# PCB_uC_Slave_Switch.net
KiCad netlist of a schematic drawn in Altium Designer
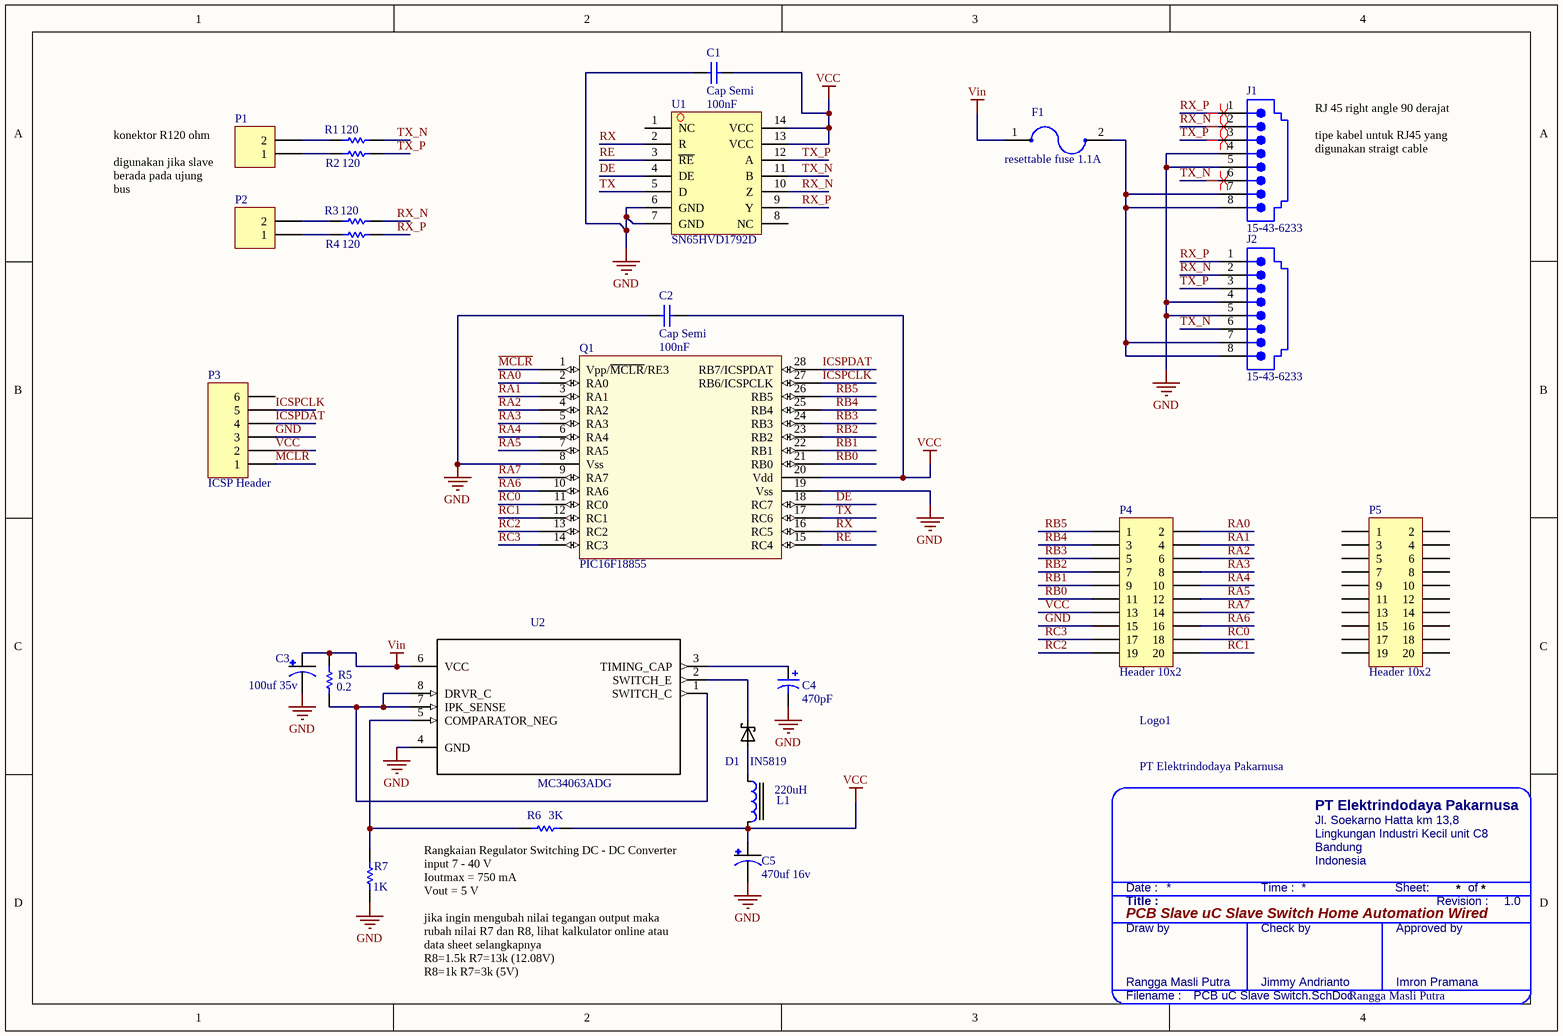
[diagram p0: PCB uC Slave Switch.SchDoc]

(export (version "E")
  (design (tool "Eeschema 10.0.6"))
  (components
    (comp (ref "C1")
      (value "Cap Semi")
      (footprint "CAPC2012M")
      (description "Capacitor (Semiconductor SIM Model)")
      (fields (field (name "ALTIUM_VALUE") "100nF") (field (name "PUBLISHER") "Altium Limited"))
      (libsource (lib "Miscellaneous Devices") (part "Cap Semi"))
    )
    (comp (ref "C2")
      (value "Cap Semi")
      (footprint "CAPC2012M")
      (description "Capacitor (Semiconductor SIM Model)")
      (fields (field (name "ALTIUM_VALUE") "100nF") (field (name "PUBLISHER") "Altium Limited"))
      (libsource (lib "Miscellaneous Devices") (part "Cap Semi"))
    )
    (comp (ref "C3")
      (value "100uf 35v")
      (footprint "OSCON_SVPF_6.3MM")
      (description "Cap, Alu Elec, 100uf, 50v, Smd")
      (fields (field (name "MP") "EDK107M050A9MAA") (field (name "MF") "Kemet"))
      (libsource (lib "RMPLib") (part "EDK107M050A9MAA"))
    )
    (comp (ref "C4")
      (value "470pF")
      (footprint "CAPC2012M")
      (description "Polarized Capacitor (Surface Mount)")
      (fields (field (name "Comment") "Cap Pol3") (field (name "PUBLISHER") "Altium Limited"))
      (libsource (lib "Miscellaneous Devices") (part "Cap Pol3"))
    )
    (comp (ref "C5")
      (value "470uf 16v")
      (footprint "CAPAE1030X1200_EEE-FC1C471AP(Primary)")
      (description "Cap, Alu Elec, 100uf, 50v, Smd")
      (fields (field (name "MP") "EDK107M050A9MAA") (field (name "MF") "Kemet"))
      (libsource (lib "RMPLib") (part "EDK107M050A9MAA"))
    )
    (comp (ref "D1")
      (value "IN5819")
      (footprint "DO-214AC_SS14(Primary)")
      (description "1a 40v Smd Schottky Rectifier")
      (fields (field (name "MF") "Taiwan Semiconductor") (field (name "MP") "SS14"))
      (libsource (lib "SS14") (part "SS14"))
    )
    (comp (ref "F1")
      (value "resettable fuse 1.1A")
      (footprint "0805")
      (description "resettable fuse 1.1A 0805")
      (fields (field (name "MF") "Littelfuse"))
      (libsource (lib "resettable fuse 1.1a 0805 ") (part "resettable fuse 1.1A 0805"))
    )
    (comp (ref "J1")
      (value "15-43-6233")
      (footprint "15-43-6233")
      (description "Right Angle, Standard Profile, RJ45-Keyed, Flange Mount PCB Jack")
      (fields (field (name "PUBLISHER") "Altium Limited"))
      (libsource (lib "newmolex modular") (part "15-43-6233"))
    )
    (comp (ref "J2")
      (value "15-43-6233")
      (footprint "15-43-6233")
      (description "Right Angle, Standard Profile, RJ45-Keyed, Flange Mount PCB Jack")
      (fields (field (name "PUBLISHER") "Altium Limited"))
      (libsource (lib "newmolex modular") (part "15-43-6233"))
    )
    (comp (ref "L1")
      (value "220uH")
      (footprint "CDRH104R")
      (description "Inductor Power Shielded Drum Core 220uH")
      (fields (field (name "MF") "Sumida") (field (name "MP") "CDRH104RNP-101NC"))
      (libsource (lib "CDRH104R") (part "CDRH104R"))
    )
    (comp (ref "Logo1")
      (value "PT Elektrindodaya Pakarnusa")
      (footprint "ElsaLogoTop")
      (description "Elsa Company Logo")
      (fields (field (name "CREATE BY") "Jimmy Andrianto"))
      (libsource (lib "JimmyLib14E") (part "ElsaLogoTopOverlay"))
    )
    (comp (ref "P1")
      (value "Header 2")
      (footprint "HDR1X2")
      (description "Header, 2-Pin")
      (fields (field (name "PUBLISHER") "Altium Limited"))
      (libsource (lib "custom connectors") (part "Header 2"))
    )
    (comp (ref "P2")
      (value "Header 2")
      (footprint "HDR1X2")
      (description "Header, 2-Pin")
      (fields (field (name "PUBLISHER") "Altium Limited"))
      (libsource (lib "custom connectors") (part "Header 2"))
    )
    (comp (ref "P3")
      (value "ICSP Header")
      (footprint "HDR1X6")
      (description "Header, 6-Pin")
      (fields (field (name "PUBLISHER") "Altium Limited"))
      (libsource (lib "custom connectors") (part "Header 6"))
    )
    (comp (ref "P4")
      (value "Header 10x2")
      (footprint "HDR2X10 pitch 2mm hole")
      (description "Header, 14-Pin, Dual row")
      (fields (field (name "PUBLISHER") "Altium Limited"))
      (libsource (lib "RMPLib") (part "Header 10x2"))
    )
    (comp (ref "P5")
      (value "Header 10x2")
      (footprint "HDR2X10 pitch 2mm hole")
      (description "Header, 14-Pin, Dual row")
      (fields (field (name "PUBLISHER") "Altium Limited"))
      (libsource (lib "RMPLib") (part "Header 10x2"))
    )
    (comp (ref "Q1")
      (value "PIC16F18855")
      (footprint "SOP65P780X200-28N")
      (description "PIC16F18855-SSOP 28 pin")
      (libsource (lib "PIC16F18855") (part "PIC16F18855"))
    )
    (comp (ref "R1")
      (value "120")
      (footprint "RESC1608M")
      (description "Resistor")
      (fields (field (name "Comment") "Res1") (field (name "PUBLISHER") "Altium Limited"))
      (libsource (lib "Miscellaneous Devices") (part "Res1"))
    )
    (comp (ref "R2")
      (value "120")
      (footprint "RESC1608M")
      (description "Resistor")
      (fields (field (name "Comment") "Res1") (field (name "PUBLISHER") "Altium Limited"))
      (libsource (lib "Miscellaneous Devices") (part "Res1"))
    )
    (comp (ref "R3")
      (value "120")
      (footprint "RESC1608M")
      (description "Resistor")
      (fields (field (name "Comment") "Res1") (field (name "PUBLISHER") "Altium Limited"))
      (libsource (lib "Miscellaneous Devices") (part "Res1"))
    )
    (comp (ref "R4")
      (value "120")
      (footprint "RESC1608M")
      (description "Resistor")
      (fields (field (name "Comment") "Res1") (field (name "PUBLISHER") "Altium Limited"))
      (libsource (lib "Miscellaneous Devices") (part "Res1"))
    )
    (comp (ref "R5")
      (value "0.2")
      (footprint "6-0805_N")
      (description "Resistor")
      (fields (field (name "Comment") "Res1") (field (name "PUBLISHER") "Altium Limited"))
      (libsource (lib "Miscellaneous Devices") (part "Res1"))
    )
    (comp (ref "R6")
      (value "3K")
      (footprint "RESC1608M")
      (description "Resistor")
      (fields (field (name "Comment") "Res1") (field (name "PUBLISHER") "Altium Limited"))
      (libsource (lib "Miscellaneous Devices") (part "Res1"))
    )
    (comp (ref "R7")
      (value "1K")
      (footprint "RESC1608M")
      (description "Resistor")
      (fields (field (name "Comment") "Res1") (field (name "PUBLISHER") "Altium Limited"))
      (libsource (lib "Miscellaneous Devices") (part "Res1"))
    )
    (comp (ref "U1")
      (value "SN65HVD1792D")
      (footprint "R-PDSO-G14")
      (libsource (lib "ranggalib") (part "SN65HVD1792D"))
    )
    (comp (ref "U2")
      (value "MC34063ADG")
      (footprint "SOIC127P600X175-8N")
      (description "MC34063A Series 40V 1.5A 100kHz Step-Up/Down/Inverting Switching Regulator-SOIC8")
      (fields (field (name "MF") "ON Semiconductor"))
      (libsource (lib "MC34063ADG") (part "MC34063ADG"))
    )
  )
  (nets
    (net (code "1") (name "/DE") (class "Default")
      (node (ref "Q1") (pin "18") (pinfunction "RC7_18") (pintype "bidirectional"))
      (node (ref "U1") (pin "4") (pinfunction "DE_4") (pintype "passive"))
    )
    (net (code "2") (name "/ICSPCLK") (class "Default")
      (node (ref "P3") (pin "5") (pinfunction "5_5") (pintype "passive"))
      (node (ref "Q1") (pin "27") (pinfunction "RB6/ICSPCLK_27") (pintype "bidirectional"))
    )
    (net (code "3") (name "/ICSPDAT") (class "Default")
      (node (ref "P3") (pin "4") (pinfunction "4_4") (pintype "passive"))
      (node (ref "Q1") (pin "28") (pinfunction "RB7/ICSPDAT_28") (pintype "bidirectional"))
    )
    (net (code "4") (name "/RA0") (class "Default")
      (node (ref "P4") (pin "2") (pinfunction "2_2") (pintype "passive"))
      (node (ref "Q1") (pin "2") (pinfunction "RA0_2") (pintype "bidirectional"))
    )
    (net (code "5") (name "/RA1") (class "Default")
      (node (ref "P4") (pin "4") (pinfunction "4_4") (pintype "passive"))
      (node (ref "Q1") (pin "3") (pinfunction "RA1_3") (pintype "bidirectional"))
    )
    (net (code "6") (name "/RA2") (class "Default")
      (node (ref "P4") (pin "6") (pinfunction "6_6") (pintype "passive"))
      (node (ref "Q1") (pin "4") (pinfunction "RA2_4") (pintype "bidirectional"))
    )
    (net (code "7") (name "/RA3") (class "Default")
      (node (ref "P4") (pin "8") (pinfunction "8_8") (pintype "passive"))
      (node (ref "Q1") (pin "5") (pinfunction "RA3_5") (pintype "bidirectional"))
    )
    (net (code "8") (name "/RA4") (class "Default")
      (node (ref "P4") (pin "10") (pinfunction "10_10") (pintype "passive"))
      (node (ref "Q1") (pin "6") (pinfunction "RA4_6") (pintype "bidirectional"))
    )
    (net (code "9") (name "/RA5") (class "Default")
      (node (ref "P4") (pin "12") (pinfunction "12_12") (pintype "passive"))
      (node (ref "Q1") (pin "7") (pinfunction "RA5_7") (pintype "bidirectional"))
    )
    (net (code "10") (name "/RA6") (class "Default")
      (node (ref "P4") (pin "16") (pinfunction "16_16") (pintype "passive"))
      (node (ref "Q1") (pin "10") (pinfunction "RA6_10") (pintype "bidirectional"))
    )
    (net (code "11") (name "/RA7") (class "Default")
      (node (ref "P4") (pin "14") (pinfunction "14_14") (pintype "passive"))
      (node (ref "Q1") (pin "9") (pinfunction "RA7_9") (pintype "bidirectional"))
    )
    (net (code "12") (name "/RB0") (class "Default")
      (node (ref "P4") (pin "11") (pinfunction "11_11") (pintype "passive"))
      (node (ref "Q1") (pin "21") (pinfunction "RB0_21") (pintype "bidirectional"))
    )
    (net (code "13") (name "/RB1") (class "Default")
      (node (ref "P4") (pin "9") (pinfunction "9_9") (pintype "passive"))
      (node (ref "Q1") (pin "22") (pinfunction "RB1_22") (pintype "bidirectional"))
    )
    (net (code "14") (name "/RB2") (class "Default")
      (node (ref "P4") (pin "7") (pinfunction "7_7") (pintype "passive"))
      (node (ref "Q1") (pin "23") (pinfunction "RB2_23") (pintype "bidirectional"))
    )
    (net (code "15") (name "/RB3") (class "Default")
      (node (ref "P4") (pin "5") (pinfunction "5_5") (pintype "passive"))
      (node (ref "Q1") (pin "24") (pinfunction "RB3_24") (pintype "bidirectional"))
    )
    (net (code "16") (name "/RB4") (class "Default")
      (node (ref "P4") (pin "3") (pinfunction "3_3") (pintype "passive"))
      (node (ref "Q1") (pin "25") (pinfunction "RB4_25") (pintype "bidirectional"))
    )
    (net (code "17") (name "/RB5") (class "Default")
      (node (ref "P4") (pin "1") (pinfunction "1_1") (pintype "passive"))
      (node (ref "Q1") (pin "26") (pinfunction "RB5_26") (pintype "bidirectional"))
    )
    (net (code "18") (name "/RC0") (class "Default")
      (node (ref "P4") (pin "18") (pinfunction "18_18") (pintype "passive"))
      (node (ref "Q1") (pin "11") (pinfunction "RC0_11") (pintype "bidirectional"))
    )
    (net (code "19") (name "/RC1") (class "Default")
      (node (ref "P4") (pin "20") (pinfunction "20_20") (pintype "passive"))
      (node (ref "Q1") (pin "12") (pinfunction "RC1_12") (pintype "bidirectional"))
    )
    (net (code "20") (name "/RC2") (class "Default")
      (node (ref "P4") (pin "19") (pinfunction "19_19") (pintype "passive"))
      (node (ref "Q1") (pin "13") (pinfunction "RC2_13") (pintype "bidirectional"))
    )
    (net (code "21") (name "/RC3") (class "Default")
      (node (ref "P4") (pin "17") (pinfunction "17_17") (pintype "passive"))
      (node (ref "Q1") (pin "14") (pinfunction "RC3_14") (pintype "bidirectional"))
    )
    (net (code "22") (name "/RE") (class "Default")
      (node (ref "Q1") (pin "15") (pinfunction "RC4_15") (pintype "bidirectional"))
      (node (ref "U1") (pin "3") (pinfunction "~{RE}_3") (pintype "passive"))
    )
    (net (code "23") (name "/RX") (class "Default")
      (node (ref "Q1") (pin "16") (pinfunction "RC5_16") (pintype "bidirectional"))
      (node (ref "U1") (pin "2") (pinfunction "R_2") (pintype "passive"))
    )
    (net (code "24") (name "/RX_N") (class "Default")
      (node (ref "J1") (pin "2") (pinfunction "2_2") (pintype "passive"))
      (node (ref "J2") (pin "2") (pinfunction "2_2") (pintype "passive"))
      (node (ref "R3") (pin "2") (pinfunction "2_2") (pintype "passive"))
      (node (ref "U1") (pin "10") (pinfunction "Z_10") (pintype "passive"))
    )
    (net (code "25") (name "/RX_P") (class "Default")
      (node (ref "J1") (pin "1") (pinfunction "1_1") (pintype "passive"))
      (node (ref "J2") (pin "1") (pinfunction "1_1") (pintype "passive"))
      (node (ref "R4") (pin "2") (pinfunction "2_2") (pintype "passive"))
      (node (ref "U1") (pin "9") (pinfunction "Y_9") (pintype "passive"))
    )
    (net (code "26") (name "/TX") (class "Default")
      (node (ref "Q1") (pin "17") (pinfunction "RC6_17") (pintype "bidirectional"))
      (node (ref "U1") (pin "5") (pinfunction "D_5") (pintype "passive"))
    )
    (net (code "27") (name "/TX_N") (class "Default")
      (node (ref "J1") (pin "6") (pinfunction "6_6") (pintype "passive"))
      (node (ref "J2") (pin "6") (pinfunction "6_6") (pintype "passive"))
      (node (ref "R1") (pin "2") (pinfunction "2_2") (pintype "passive"))
      (node (ref "U1") (pin "11") (pinfunction "B_11") (pintype "passive"))
    )
    (net (code "28") (name "/TX_P") (class "Default")
      (node (ref "J1") (pin "3") (pinfunction "3_3") (pintype "passive"))
      (node (ref "J2") (pin "3") (pinfunction "3_3") (pintype "passive"))
      (node (ref "R2") (pin "2") (pinfunction "2_2") (pintype "passive"))
      (node (ref "U1") (pin "12") (pinfunction "A_12") (pintype "passive"))
    )
    (net (code "29") (name "/~{MCLR}") (class "Default")
      (node (ref "P3") (pin "1") (pinfunction "1_1") (pintype "passive"))
      (node (ref "Q1") (pin "1") (pinfunction "Vpp/~{MCLR}/RE3_1") (pintype "bidirectional"))
    )
    (net (code "30") (name "GND") (class "Default")
      (node (ref "C1") (pin "1") (pinfunction "1_1") (pintype "passive"))
      (node (ref "C2") (pin "1") (pinfunction "1_1") (pintype "passive"))
      (node (ref "C3") (pin "NEG") (pinfunction "NEG_NEG") (pintype "passive"))
      (node (ref "C4") (pin "2") (pinfunction "2_2") (pintype "passive"))
      (node (ref "C5") (pin "NEG") (pinfunction "NEG_NEG") (pintype "passive"))
      (node (ref "J1") (pin "4") (pinfunction "4_4") (pintype "passive"))
      (node (ref "J1") (pin "5") (pinfunction "5_5") (pintype "passive"))
      (node (ref "J2") (pin "4") (pinfunction "4_4") (pintype "passive"))
      (node (ref "J2") (pin "5") (pinfunction "5_5") (pintype "passive"))
      (node (ref "P3") (pin "3") (pinfunction "3_3") (pintype "passive"))
      (node (ref "P4") (pin "15") (pinfunction "15_15") (pintype "passive"))
      (node (ref "Q1") (pin "19") (pinfunction "Vss_19") (pintype "power_in"))
      (node (ref "Q1") (pin "8") (pinfunction "Vss_8") (pintype "power_in"))
      (node (ref "R7") (pin "1") (pinfunction "1_1") (pintype "passive"))
      (node (ref "U1") (pin "6") (pinfunction "GND_6") (pintype "passive"))
      (node (ref "U1") (pin "7") (pinfunction "GND_7") (pintype "passive"))
      (node (ref "U2") (pin "4") (pinfunction "GND_4") (pintype "passive"))
    )
    (net (code "31") (name "Net-(D1-PadA)") (class "Default")
      (node (ref "D1") (pin "A") (pinfunction "A_A") (pintype "passive"))
      (node (ref "L1") (pin "1") (pinfunction "1_1") (pintype "passive"))
    )
    (net (code "32") (name "Net-(F1-Pad2)") (class "Default")
      (node (ref "F1") (pin "2") (pinfunction "2_2") (pintype "passive"))
      (node (ref "J1") (pin "7") (pinfunction "7_7") (pintype "passive"))
      (node (ref "J1") (pin "8") (pinfunction "8_8") (pintype "passive"))
      (node (ref "J2") (pin "7") (pinfunction "7_7") (pintype "passive"))
      (node (ref "J2") (pin "8") (pinfunction "8_8") (pintype "passive"))
    )
    (net (code "33") (name "Net-(P1-Pad1)") (class "Default")
      (node (ref "P1") (pin "1") (pinfunction "1_1") (pintype "passive"))
      (node (ref "R2") (pin "1") (pinfunction "1_1") (pintype "passive"))
    )
    (net (code "34") (name "Net-(P1-Pad2)") (class "Default")
      (node (ref "P1") (pin "2") (pinfunction "2_2") (pintype "passive"))
      (node (ref "R1") (pin "1") (pinfunction "1_1") (pintype "passive"))
    )
    (net (code "35") (name "Net-(P2-Pad1)") (class "Default")
      (node (ref "P2") (pin "1") (pinfunction "1_1") (pintype "passive"))
      (node (ref "R4") (pin "1") (pinfunction "1_1") (pintype "passive"))
    )
    (net (code "36") (name "Net-(P2-Pad2)") (class "Default")
      (node (ref "P2") (pin "2") (pinfunction "2_2") (pintype "passive"))
      (node (ref "R3") (pin "1") (pinfunction "1_1") (pintype "passive"))
    )
    (net (code "37") (name "Net-(U2-COMPARATOR_NEG)") (class "Default")
      (node (ref "R6") (pin "1") (pinfunction "1_1") (pintype "passive"))
      (node (ref "R7") (pin "2") (pinfunction "2_2") (pintype "passive"))
      (node (ref "U2") (pin "5") (pinfunction "COMPARATOR_NEG_5") (pintype "input"))
    )
    (net (code "38") (name "Net-(U2-DRVR_C)") (class "Default")
      (node (ref "R5") (pin "1") (pinfunction "1_1") (pintype "passive"))
      (node (ref "U2") (pin "1") (pinfunction "SWITCH_C_1") (pintype "output"))
      (node (ref "U2") (pin "7") (pinfunction "IPK_SENSE_7") (pintype "input"))
      (node (ref "U2") (pin "8") (pinfunction "DRVR_C_8") (pintype "input"))
    )
    (net (code "39") (name "Net-(U2-SWITCH_E)") (class "Default")
      (node (ref "D1") (pin "C") (pinfunction "C_C") (pintype "passive"))
      (node (ref "U2") (pin "2") (pinfunction "SWITCH_E_2") (pintype "output"))
    )
    (net (code "40") (name "Net-(U2-TIMING_CAP)") (class "Default")
      (node (ref "C4") (pin "1") (pinfunction "1_1") (pintype "passive"))
      (node (ref "U2") (pin "3") (pinfunction "TIMING_CAP_3") (pintype "output"))
    )
    (net (code "41") (name "VCC") (class "Default")
      (node (ref "C1") (pin "2") (pinfunction "2_2") (pintype "passive"))
      (node (ref "C2") (pin "2") (pinfunction "2_2") (pintype "passive"))
      (node (ref "C5") (pin "POS") (pinfunction "POS_POS") (pintype "passive"))
      (node (ref "L1") (pin "2") (pinfunction "2_2") (pintype "passive"))
      (node (ref "P3") (pin "2") (pinfunction "2_2") (pintype "passive"))
      (node (ref "P4") (pin "13") (pinfunction "13_13") (pintype "passive"))
      (node (ref "Q1") (pin "20") (pinfunction "Vdd_20") (pintype "power_in"))
      (node (ref "R6") (pin "2") (pinfunction "2_2") (pintype "passive"))
      (node (ref "U1") (pin "13") (pinfunction "VCC_13") (pintype "passive"))
      (node (ref "U1") (pin "14") (pinfunction "VCC_14") (pintype "passive"))
    )
    (net (code "42") (name "Vin") (class "Default")
      (node (ref "C3") (pin "POS") (pinfunction "POS_POS") (pintype "passive"))
      (node (ref "F1") (pin "1") (pinfunction "1_1") (pintype "passive"))
      (node (ref "R5") (pin "2") (pinfunction "2_2") (pintype "passive"))
      (node (ref "U2") (pin "6") (pinfunction "VCC_6") (pintype "power_in"))
    )
    (net (code "43") (name "unconnected-(P3-Pad6)") (class "Default")
      (node (ref "P3") (pin "6") (pinfunction "6_6") (pintype "passive"))
    )
    (net (code "44") (name "unconnected-(P5-Pad1)") (class "Default")
      (node (ref "P5") (pin "1") (pinfunction "1_1") (pintype "passive"))
    )
    (net (code "45") (name "unconnected-(P5-Pad2)") (class "Default")
      (node (ref "P5") (pin "2") (pinfunction "2_2") (pintype "passive"))
    )
    (net (code "46") (name "unconnected-(P5-Pad3)") (class "Default")
      (node (ref "P5") (pin "3") (pinfunction "3_3") (pintype "passive"))
    )
    (net (code "47") (name "unconnected-(P5-Pad4)") (class "Default")
      (node (ref "P5") (pin "4") (pinfunction "4_4") (pintype "passive"))
    )
    (net (code "48") (name "unconnected-(P5-Pad5)") (class "Default")
      (node (ref "P5") (pin "5") (pinfunction "5_5") (pintype "passive"))
    )
    (net (code "49") (name "unconnected-(P5-Pad6)") (class "Default")
      (node (ref "P5") (pin "6") (pinfunction "6_6") (pintype "passive"))
    )
    (net (code "50") (name "unconnected-(P5-Pad7)") (class "Default")
      (node (ref "P5") (pin "7") (pinfunction "7_7") (pintype "passive"))
    )
    (net (code "51") (name "unconnected-(P5-Pad8)") (class "Default")
      (node (ref "P5") (pin "8") (pinfunction "8_8") (pintype "passive"))
    )
    (net (code "52") (name "unconnected-(P5-Pad9)") (class "Default")
      (node (ref "P5") (pin "9") (pinfunction "9_9") (pintype "passive"))
    )
    (net (code "53") (name "unconnected-(P5-Pad10)") (class "Default")
      (node (ref "P5") (pin "10") (pinfunction "10_10") (pintype "passive"))
    )
    (net (code "54") (name "unconnected-(P5-Pad11)") (class "Default")
      (node (ref "P5") (pin "11") (pinfunction "11_11") (pintype "passive"))
    )
    (net (code "55") (name "unconnected-(P5-Pad12)") (class "Default")
      (node (ref "P5") (pin "12") (pinfunction "12_12") (pintype "passive"))
    )
    (net (code "56") (name "unconnected-(P5-Pad13)") (class "Default")
      (node (ref "P5") (pin "13") (pinfunction "13_13") (pintype "passive"))
    )
    (net (code "57") (name "unconnected-(P5-Pad14)") (class "Default")
      (node (ref "P5") (pin "14") (pinfunction "14_14") (pintype "passive"))
    )
    (net (code "58") (name "unconnected-(P5-Pad15)") (class "Default")
      (node (ref "P5") (pin "15") (pinfunction "15_15") (pintype "passive"))
    )
    (net (code "59") (name "unconnected-(P5-Pad16)") (class "Default")
      (node (ref "P5") (pin "16") (pinfunction "16_16") (pintype "passive"))
    )
    (net (code "60") (name "unconnected-(P5-Pad17)") (class "Default")
      (node (ref "P5") (pin "17") (pinfunction "17_17") (pintype "passive"))
    )
    (net (code "61") (name "unconnected-(P5-Pad18)") (class "Default")
      (node (ref "P5") (pin "18") (pinfunction "18_18") (pintype "passive"))
    )
    (net (code "62") (name "unconnected-(P5-Pad19)") (class "Default")
      (node (ref "P5") (pin "19") (pinfunction "19_19") (pintype "passive"))
    )
    (net (code "63") (name "unconnected-(P5-Pad20)") (class "Default")
      (node (ref "P5") (pin "20") (pinfunction "20_20") (pintype "passive"))
    )
    (net (code "64") (name "unconnected-(U1-NC-Pad1)") (class "Default")
      (node (ref "U1") (pin "1") (pinfunction "NC_1") (pintype "passive"))
    )
    (net (code "65") (name "unconnected-(U1-NC-Pad8)") (class "Default")
      (node (ref "U1") (pin "8") (pinfunction "NC_8") (pintype "passive"))
    )
  )
)
